# SmartIMU_TestBoard_Sch.net
KiCad netlist of a schematic drawn in Altium Designer
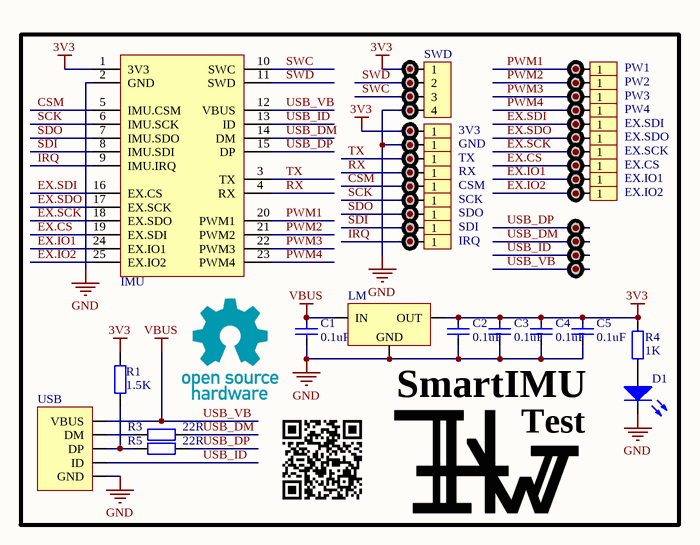
[diagram p0: SmartIMU_TestBoard_Sch.SchDoc]

(export (version "E")
  (design (tool "Eeschema 10.0.6"))
  (components
    (comp (ref "3V3")
      (value "HDR1X1_180_2.54")
      (footprint "PCB_Connector:HDR1X1_180_2.54")
      (description "Header")
      (libsource (lib "SCH_Connector") (part "HDR1X1_180_2.54"))
    )
    (comp (ref "C1")
      (value "0.1uF")
      (footprint "PCB_Passive:CAP_0603")
      (description "Capacitor")
      (fields (field (name "Comment") "Cap_0603"))
      (libsource (lib "SCH_Passive") (part "Cap_0603"))
    )
    (comp (ref "C2")
      (value "0.1uF")
      (footprint "PCB_Passive:CAP_0603")
      (description "Capacitor")
      (fields (field (name "Comment") "Cap_0603"))
      (libsource (lib "SCH_Passive") (part "Cap_0603"))
    )
    (comp (ref "C3")
      (value "0.1uF")
      (footprint "PCB_Passive:CAP_0603")
      (description "Capacitor")
      (fields (field (name "Comment") "Cap_0603"))
      (libsource (lib "SCH_Passive") (part "Cap_0603"))
    )
    (comp (ref "C4")
      (value "0.1uF")
      (footprint "PCB_Passive:CAP_0603")
      (description "Capacitor")
      (fields (field (name "Comment") "Cap_0603"))
      (libsource (lib "SCH_Passive") (part "Cap_0603"))
    )
    (comp (ref "C5")
      (value "0.1uF")
      (footprint "PCB_Passive:CAP_0603")
      (description "Capacitor")
      (fields (field (name "Comment") "Cap_0603"))
      (libsource (lib "SCH_Passive") (part "Cap_0603"))
    )
    (comp (ref "CSM")
      (value "HDR1X1_180_2.54")
      (footprint "PCB_Connector:HDR1X1_180_2.54")
      (description "Header")
      (libsource (lib "SCH_Connector") (part "HDR1X1_180_2.54"))
    )
    (comp (ref "D1")
      (value "LED_0603_BLUE")
      (footprint "PCB_Active:LED_0603_BLUE")
      (description "LED")
      (libsource (lib "SCH_Active") (part "LED_0603_BLUE"))
    )
    (comp (ref "EX.CS")
      (value "HDR1X1_180_2.54")
      (footprint "PCB_Connector:HDR1X1_180_2.54")
      (description "Header")
      (libsource (lib "SCH_Connector") (part "HDR1X1_180_2.54"))
    )
    (comp (ref "EX.IO1")
      (value "HDR1X1_180_2.54")
      (footprint "PCB_Connector:HDR1X1_180_2.54")
      (description "Header")
      (libsource (lib "SCH_Connector") (part "HDR1X1_180_2.54"))
    )
    (comp (ref "EX.IO2")
      (value "HDR1X1_180_2.54")
      (footprint "PCB_Connector:HDR1X1_180_2.54")
      (description "Header")
      (libsource (lib "SCH_Connector") (part "HDR1X1_180_2.54"))
    )
    (comp (ref "EX.SCK")
      (value "HDR1X1_180_2.54")
      (footprint "PCB_Connector:HDR1X1_180_2.54")
      (description "Header")
      (libsource (lib "SCH_Connector") (part "HDR1X1_180_2.54"))
    )
    (comp (ref "EX.SDI")
      (value "HDR1X1_180_2.54")
      (footprint "PCB_Connector:HDR1X1_180_2.54")
      (description "Header")
      (libsource (lib "SCH_Connector") (part "HDR1X1_180_2.54"))
    )
    (comp (ref "EX.SDO")
      (value "HDR1X1_180_2.54")
      (footprint "PCB_Connector:HDR1X1_180_2.54")
      (description "Header")
      (libsource (lib "SCH_Connector") (part "HDR1X1_180_2.54"))
    )
    (comp (ref "GND")
      (value "HDR1X1_180_2.54")
      (footprint "PCB_Connector:HDR1X1_180_2.54")
      (description "Header")
      (libsource (lib "SCH_Connector") (part "HDR1X1_180_2.54"))
    )
    (comp (ref "HW")
      (value "HW")
      (footprint "PCB_Logo:Logo_HW_v2.0")
      (description "Logo")
      (libsource (lib "SCH_Logo") (part "HW"))
    )
    (comp (ref "IMU")
      (value "SmartIMU_Full")
      (footprint "PCB_Module:SMART_IMU_FULL")
      (description "Module")
      (libsource (lib "SCH_Module") (part "SmartIMU_Full"))
    )
    (comp (ref "IRQ")
      (value "HDR1X1_180_2.54")
      (footprint "PCB_Connector:HDR1X1_180_2.54")
      (description "Header")
      (libsource (lib "SCH_Connector") (part "HDR1X1_180_2.54"))
    )
    (comp (ref "LM")
      (value "LM1117")
      (footprint "PCB_IC:SOT223")
      (description "Power")
      (libsource (lib "SCH_IC") (part "LM1117"))
    )
    (comp (ref "ORCODE")
      (value "SmartIMU_ORCODE")
      (description "Logo")
      (libsource (lib "SCH_Logo") (part "SmartIMU_ORCODE"))
    )
    (comp (ref "OSHW") (value "OSHW") (description "Logo") (libsource (lib "SCH_Logo") (part "OSHW")))
    (comp (ref "PW1")
      (value "HDR1X1_180_2.54")
      (footprint "PCB_Connector:HDR1X1_180_2.54")
      (description "Header")
      (libsource (lib "SCH_Connector") (part "HDR1X1_180_2.54"))
    )
    (comp (ref "PW2")
      (value "HDR1X1_180_2.54")
      (footprint "PCB_Connector:HDR1X1_180_2.54")
      (description "Header")
      (libsource (lib "SCH_Connector") (part "HDR1X1_180_2.54"))
    )
    (comp (ref "PW3")
      (value "HDR1X1_180_2.54")
      (footprint "PCB_Connector:HDR1X1_180_2.54")
      (description "Header")
      (libsource (lib "SCH_Connector") (part "HDR1X1_180_2.54"))
    )
    (comp (ref "PW4")
      (value "HDR1X1_180_2.54")
      (footprint "PCB_Connector:HDR1X1_180_2.54")
      (description "Header")
      (libsource (lib "SCH_Connector") (part "HDR1X1_180_2.54"))
    )
    (comp (ref "R1")
      (value "1.5K")
      (footprint "PCB_Passive:RES_0603")
      (description "Resistor")
      (fields (field (name "Comment") "Res_0603"))
      (libsource (lib "SCH_Passive") (part "Res_0603"))
    )
    (comp (ref "R3")
      (value "22R")
      (footprint "PCB_Passive:RES_0603")
      (description "Resistor")
      (fields (field (name "Comment") "Res_0603"))
      (libsource (lib "") (part "Res_0603_1"))
    )
    (comp (ref "R4")
      (value "1K")
      (footprint "PCB_Passive:RES_0603")
      (description "Resistor")
      (fields (field (name "Comment") "Res_0603"))
      (libsource (lib "SCH_Passive") (part "Res_0603"))
    )
    (comp (ref "R5")
      (value "22R")
      (footprint "PCB_Passive:RES_0603")
      (description "Resistor")
      (fields (field (name "Comment") "Res_0603"))
      (libsource (lib "") (part "Res_0603_1"))
    )
    (comp (ref "RX")
      (value "HDR1X1_180_2.54")
      (footprint "PCB_Connector:HDR1X1_180_2.54")
      (description "Header")
      (libsource (lib "SCH_Connector") (part "HDR1X1_180_2.54"))
    )
    (comp (ref "SCK")
      (value "HDR1X1_180_2.54")
      (footprint "PCB_Connector:HDR1X1_180_2.54")
      (description "Header")
      (libsource (lib "SCH_Connector") (part "HDR1X1_180_2.54"))
    )
    (comp (ref "SDI")
      (value "HDR1X1_180_2.54")
      (footprint "PCB_Connector:HDR1X1_180_2.54")
      (description "Header")
      (libsource (lib "SCH_Connector") (part "HDR1X1_180_2.54"))
    )
    (comp (ref "SDO")
      (value "HDR1X1_180_2.54")
      (footprint "PCB_Connector:HDR1X1_180_2.54")
      (description "Header")
      (libsource (lib "SCH_Connector") (part "HDR1X1_180_2.54"))
    )
    (comp (ref "SWD")
      (value "HDR1X4_90F_2.54")
      (footprint "PCB_Connector:HDR1X4_90F_2.54")
      (description "Header")
      (libsource (lib "SCH_Connector") (part "HDR1X4_90F_2.54"))
    )
    (comp (ref "TP1")
      (value "TestPoint_HalfH")
      (footprint "PCB_Connector:TestPoint_0.6mm_HelfH")
      (description "TestPoint")
      (libsource (lib "SCH_Connector") (part "TestPoint_HalfH"))
    )
    (comp (ref "TP2")
      (value "TestPoint_HalfH")
      (footprint "PCB_Connector:TestPoint_0.6mm_HelfH")
      (description "TestPoint")
      (libsource (lib "SCH_Connector") (part "TestPoint_HalfH"))
    )
    (comp (ref "TP3")
      (value "TestPoint_HalfH")
      (footprint "PCB_Connector:TestPoint_0.6mm_HelfH")
      (description "TestPoint")
      (libsource (lib "SCH_Connector") (part "TestPoint_HalfH"))
    )
    (comp (ref "TP4")
      (value "TestPoint_HalfH")
      (footprint "PCB_Connector:TestPoint_0.6mm_HelfH")
      (description "TestPoint")
      (libsource (lib "SCH_Connector") (part "TestPoint_HalfH"))
    )
    (comp (ref "TP5")
      (value "TestPoint_HalfH")
      (footprint "PCB_Connector:TestPoint_0.6mm_HelfH")
      (description "TestPoint")
      (libsource (lib "SCH_Connector") (part "TestPoint_HalfH"))
    )
    (comp (ref "TP6")
      (value "TestPoint_HalfH")
      (footprint "PCB_Connector:TestPoint_0.6mm_HelfH")
      (description "TestPoint")
      (libsource (lib "SCH_Connector") (part "TestPoint_HalfH"))
    )
    (comp (ref "TP7")
      (value "TestPoint_HalfH")
      (footprint "PCB_Connector:TestPoint_0.6mm_HelfH")
      (description "TestPoint")
      (libsource (lib "SCH_Connector") (part "TestPoint_HalfH"))
    )
    (comp (ref "TP8")
      (value "TestPoint_HalfH")
      (footprint "PCB_Connector:TestPoint_0.6mm_HelfH")
      (description "TestPoint")
      (libsource (lib "SCH_Connector") (part "TestPoint_HalfH"))
    )
    (comp (ref "TP9")
      (value "TestPoint_HalfH")
      (footprint "PCB_Connector:TestPoint_0.6mm_HelfH")
      (description "TestPoint")
      (libsource (lib "SCH_Connector") (part "TestPoint_HalfH"))
    )
    (comp (ref "TP10")
      (value "TestPoint_HalfH")
      (footprint "PCB_Connector:TestPoint_0.6mm_HelfH")
      (description "TestPoint")
      (libsource (lib "SCH_Connector") (part "TestPoint_HalfH"))
    )
    (comp (ref "TP11")
      (value "TestPoint_HalfH")
      (footprint "PCB_Connector:TestPoint_0.6mm_HelfH")
      (description "TestPoint")
      (libsource (lib "SCH_Connector") (part "TestPoint_HalfH"))
    )
    (comp (ref "TP12")
      (value "TestPoint_HalfH")
      (footprint "PCB_Connector:TestPoint_0.6mm_HelfH")
      (description "TestPoint")
      (libsource (lib "SCH_Connector") (part "TestPoint_HalfH"))
    )
    (comp (ref "TP13")
      (value "TestPoint_HalfH")
      (footprint "PCB_Connector:TestPoint_0.6mm_HelfH")
      (description "TestPoint")
      (libsource (lib "SCH_Connector") (part "TestPoint_HalfH"))
    )
    (comp (ref "TP14")
      (value "TestPoint_HalfH")
      (footprint "PCB_Connector:TestPoint_0.6mm_HelfH")
      (description "TestPoint")
      (libsource (lib "SCH_Connector") (part "TestPoint_HalfH"))
    )
    (comp (ref "TP15")
      (value "TestPoint_HalfH")
      (footprint "PCB_Connector:TestPoint_0.6mm_HelfH")
      (description "TestPoint")
      (libsource (lib "SCH_Connector") (part "TestPoint_HalfH"))
    )
    (comp (ref "TP16")
      (value "TestPoint_HalfH")
      (footprint "PCB_Connector:TestPoint_0.6mm_HelfH")
      (description "TestPoint")
      (libsource (lib "SCH_Connector") (part "TestPoint_HalfH"))
    )
    (comp (ref "TP17")
      (value "TestPoint_HalfH")
      (footprint "PCB_Connector:TestPoint_0.6mm_HelfH")
      (description "TestPoint")
      (libsource (lib "SCH_Connector") (part "TestPoint_HalfH"))
    )
    (comp (ref "TP18")
      (value "TestPoint_HalfH")
      (footprint "PCB_Connector:TestPoint_0.6mm_HelfH")
      (description "TestPoint")
      (libsource (lib "SCH_Connector") (part "TestPoint_HalfH"))
    )
    (comp (ref "TP19")
      (value "TestPoint_HalfH")
      (footprint "PCB_Connector:TestPoint_0.6mm_HelfH")
      (description "TestPoint")
      (libsource (lib "SCH_Connector") (part "TestPoint_HalfH"))
    )
    (comp (ref "TP20")
      (value "TestPoint_HalfH")
      (footprint "PCB_Connector:TestPoint_0.6mm_HelfH")
      (description "TestPoint")
      (libsource (lib "SCH_Connector") (part "TestPoint_HalfH"))
    )
    (comp (ref "TP21")
      (value "TestPoint_HalfH")
      (footprint "PCB_Connector:TestPoint_0.6mm_HelfH")
      (description "TestPoint")
      (libsource (lib "SCH_Connector") (part "TestPoint_HalfH"))
    )
    (comp (ref "TP22")
      (value "TestPoint_HalfH")
      (footprint "PCB_Connector:TestPoint_0.6mm_HelfH")
      (description "TestPoint")
      (libsource (lib "SCH_Connector") (part "TestPoint_HalfH"))
    )
    (comp (ref "TP23")
      (value "TestPoint_HalfH")
      (footprint "PCB_Connector:TestPoint_0.6mm_HelfH")
      (description "TestPoint")
      (libsource (lib "SCH_Connector") (part "TestPoint_HalfH"))
    )
    (comp (ref "TP24")
      (value "TestPoint_HalfH")
      (footprint "PCB_Connector:TestPoint_0.6mm_HelfH")
      (description "TestPoint")
      (libsource (lib "SCH_Connector") (part "TestPoint_HalfH"))
    )
    (comp (ref "TP25")
      (value "TestPoint_HalfH")
      (footprint "PCB_Connector:TestPoint_0.6mm_HelfH")
      (description "TestPoint")
      (libsource (lib "SCH_Connector") (part "TestPoint_HalfH"))
    )
    (comp (ref "TP26")
      (value "TestPoint_HalfH")
      (footprint "PCB_Connector:TestPoint_0.6mm_HelfH")
      (description "TestPoint")
      (libsource (lib "SCH_Connector") (part "TestPoint_HalfH"))
    )
    (comp (ref "TP27")
      (value "TestPoint_HalfH")
      (footprint "PCB_Connector:TestPoint_0.6mm_HelfH")
      (description "TestPoint")
      (libsource (lib "SCH_Connector") (part "TestPoint_HalfH"))
    )
    (comp (ref "TX")
      (value "HDR1X1_180_2.54")
      (footprint "PCB_Connector:HDR1X1_180_2.54")
      (description "Header")
      (libsource (lib "SCH_Connector") (part "HDR1X1_180_2.54"))
    )
    (comp (ref "USB")
      (value "USB_Micro")
      (footprint "PCB_USB:USB_Micro-AB")
      (description "USB")
      (libsource (lib "SCH_USB") (part "USB_Micro"))
    )
  )
  (nets
    (net (code "1") (name "/CSM") (class "Default")
      (node (ref "CSM") (pin "1") (pinfunction "1_1") (pintype "passive"))
      (node (ref "IMU") (pin "5") (pinfunction "IMU.CSM_5") (pintype "passive"))
      (node (ref "TP7") (pin "1") (pinfunction "TP_1") (pintype "passive"))
    )
    (net (code "2") (name "/EX.CS") (class "Default")
      (node (ref "EX.CS") (pin "1") (pinfunction "1_1") (pintype "passive"))
      (node (ref "IMU") (pin "19") (pinfunction "EX.SDI_19") (pintype "passive"))
      (node (ref "TP21") (pin "1") (pinfunction "TP_1") (pintype "passive"))
    )
    (net (code "3") (name "/EX.IO1") (class "Default")
      (node (ref "EX.IO1") (pin "1") (pinfunction "1_1") (pintype "passive"))
      (node (ref "IMU") (pin "24") (pinfunction "EX.IO1_24") (pintype "passive"))
      (node (ref "TP22") (pin "1") (pinfunction "TP_1") (pintype "passive"))
    )
    (net (code "4") (name "/EX.IO2") (class "Default")
      (node (ref "EX.IO2") (pin "1") (pinfunction "1_1") (pintype "passive"))
      (node (ref "IMU") (pin "25") (pinfunction "EX.IO2_25") (pintype "passive"))
      (node (ref "TP23") (pin "1") (pinfunction "TP_1") (pintype "passive"))
    )
    (net (code "5") (name "/EX.SCK") (class "Default")
      (node (ref "EX.SCK") (pin "1") (pinfunction "1_1") (pintype "passive"))
      (node (ref "IMU") (pin "18") (pinfunction "EX.SDO_18") (pintype "passive"))
      (node (ref "TP20") (pin "1") (pinfunction "TP_1") (pintype "passive"))
    )
    (net (code "6") (name "/EX.SDI") (class "Default")
      (node (ref "EX.SDI") (pin "1") (pinfunction "1_1") (pintype "passive"))
      (node (ref "IMU") (pin "16") (pinfunction "EX.CS_16") (pintype "passive"))
      (node (ref "TP18") (pin "1") (pinfunction "TP_1") (pintype "passive"))
    )
    (net (code "7") (name "/EX.SDO") (class "Default")
      (node (ref "EX.SDO") (pin "1") (pinfunction "1_1") (pintype "passive"))
      (node (ref "IMU") (pin "17") (pinfunction "EX.SCK_17") (pintype "passive"))
      (node (ref "TP19") (pin "1") (pinfunction "TP_1") (pintype "passive"))
    )
    (net (code "8") (name "/IRQ") (class "Default")
      (node (ref "IMU") (pin "9") (pinfunction "IMU.IRQ_9") (pintype "passive"))
      (node (ref "IRQ") (pin "1") (pinfunction "1_1") (pintype "passive"))
      (node (ref "TP11") (pin "1") (pinfunction "TP_1") (pintype "passive"))
    )
    (net (code "9") (name "/PWM1") (class "Default")
      (node (ref "IMU") (pin "20") (pinfunction "PWM1_20") (pintype "passive"))
      (node (ref "PW1") (pin "1") (pinfunction "1_1") (pintype "passive"))
      (node (ref "TP14") (pin "1") (pinfunction "TP_1") (pintype "passive"))
    )
    (net (code "10") (name "/PWM2") (class "Default")
      (node (ref "IMU") (pin "21") (pinfunction "PWM2_21") (pintype "passive"))
      (node (ref "PW2") (pin "1") (pinfunction "1_1") (pintype "passive"))
      (node (ref "TP15") (pin "1") (pinfunction "TP_1") (pintype "passive"))
    )
    (net (code "11") (name "/PWM3") (class "Default")
      (node (ref "IMU") (pin "22") (pinfunction "PWM3_22") (pintype "passive"))
      (node (ref "PW3") (pin "1") (pinfunction "1_1") (pintype "passive"))
      (node (ref "TP16") (pin "1") (pinfunction "TP_1") (pintype "passive"))
    )
    (net (code "12") (name "/PWM4") (class "Default")
      (node (ref "IMU") (pin "23") (pinfunction "PWM4_23") (pintype "passive"))
      (node (ref "PW4") (pin "1") (pinfunction "1_1") (pintype "passive"))
      (node (ref "TP17") (pin "1") (pinfunction "TP_1") (pintype "passive"))
    )
    (net (code "13") (name "/RX") (class "Default")
      (node (ref "IMU") (pin "4") (pinfunction "RX_4") (pintype "passive"))
      (node (ref "RX") (pin "1") (pinfunction "1_1") (pintype "passive"))
      (node (ref "TP12") (pin "1") (pinfunction "TP_1") (pintype "passive"))
    )
    (net (code "14") (name "/SCK") (class "Default")
      (node (ref "IMU") (pin "6") (pinfunction "IMU.SCK_6") (pintype "passive"))
      (node (ref "SCK") (pin "1") (pinfunction "1_1") (pintype "passive"))
      (node (ref "TP8") (pin "1") (pinfunction "TP_1") (pintype "passive"))
    )
    (net (code "15") (name "/SDI") (class "Default")
      (node (ref "IMU") (pin "8") (pinfunction "IMU.SDI_8") (pintype "passive"))
      (node (ref "SDI") (pin "1") (pinfunction "1_1") (pintype "passive"))
      (node (ref "TP10") (pin "1") (pinfunction "TP_1") (pintype "passive"))
    )
    (net (code "16") (name "/SDO") (class "Default")
      (node (ref "IMU") (pin "7") (pinfunction "IMU.SDO_7") (pintype "passive"))
      (node (ref "SDO") (pin "1") (pinfunction "1_1") (pintype "passive"))
      (node (ref "TP9") (pin "1") (pinfunction "TP_1") (pintype "passive"))
    )
    (net (code "17") (name "/SWC") (class "Default")
      (node (ref "IMU") (pin "10") (pinfunction "SWC_10") (pintype "passive"))
      (node (ref "SWD") (pin "3") (pinfunction "3_3") (pintype "passive"))
      (node (ref "TP3") (pin "1") (pinfunction "TP_1") (pintype "passive"))
    )
    (net (code "18") (name "/SWD") (class "Default")
      (node (ref "IMU") (pin "11") (pinfunction "SWD_11") (pintype "passive"))
      (node (ref "SWD") (pin "2") (pinfunction "2_2") (pintype "passive"))
      (node (ref "TP2") (pin "1") (pinfunction "TP_1") (pintype "passive"))
    )
    (net (code "19") (name "/TX") (class "Default")
      (node (ref "IMU") (pin "3") (pinfunction "TX_3") (pintype "passive"))
      (node (ref "TP13") (pin "1") (pinfunction "TP_1") (pintype "passive"))
      (node (ref "TX") (pin "1") (pinfunction "1_1") (pintype "passive"))
    )
    (net (code "20") (name "/USB_DM") (class "Default")
      (node (ref "IMU") (pin "14") (pinfunction "DM_14") (pintype "passive"))
      (node (ref "R3") (pin "2") (pinfunction "2_2") (pintype "passive"))
      (node (ref "TP25") (pin "1") (pinfunction "TP_1") (pintype "passive"))
    )
    (net (code "21") (name "/USB_DP") (class "Default")
      (node (ref "IMU") (pin "15") (pinfunction "DP_15") (pintype "passive"))
      (node (ref "R5") (pin "2") (pinfunction "2_2") (pintype "passive"))
      (node (ref "TP24") (pin "1") (pinfunction "TP_1") (pintype "passive"))
    )
    (net (code "22") (name "/USB_ID") (class "Default")
      (node (ref "IMU") (pin "13") (pinfunction "ID_13") (pintype "passive"))
      (node (ref "TP26") (pin "1") (pinfunction "TP_1") (pintype "passive"))
      (node (ref "USB") (pin "4") (pinfunction "ID_4") (pintype "passive"))
    )
    (net (code "23") (name "3V3") (class "Default")
      (node (ref "3V3") (pin "1") (pinfunction "1_1") (pintype "passive"))
      (node (ref "C2") (pin "2") (pinfunction "2_2") (pintype "passive"))
      (node (ref "C3") (pin "2") (pinfunction "2_2") (pintype "passive"))
      (node (ref "C4") (pin "2") (pinfunction "2_2") (pintype "passive"))
      (node (ref "C5") (pin "2") (pinfunction "2_2") (pintype "passive"))
      (node (ref "IMU") (pin "1") (pinfunction "3V3_1") (pintype "passive"))
      (node (ref "LM") (pin "2") (pinfunction "OUT_2") (pintype "power_in"))
      (node (ref "R1") (pin "2") (pinfunction "2_2") (pintype "passive"))
      (node (ref "R4") (pin "2") (pinfunction "2_2") (pintype "passive"))
      (node (ref "SWD") (pin "1") (pinfunction "1_1") (pintype "passive"))
      (node (ref "TP1") (pin "1") (pinfunction "TP_1") (pintype "passive"))
      (node (ref "TP5") (pin "1") (pinfunction "TP_1") (pintype "passive"))
    )
    (net (code "24") (name "GND") (class "Default")
      (node (ref "C1") (pin "2") (pinfunction "2_2") (pintype "passive"))
      (node (ref "C2") (pin "1") (pinfunction "1_1") (pintype "passive"))
      (node (ref "C3") (pin "1") (pinfunction "1_1") (pintype "passive"))
      (node (ref "C4") (pin "1") (pinfunction "1_1") (pintype "passive"))
      (node (ref "C5") (pin "1") (pinfunction "1_1") (pintype "passive"))
      (node (ref "D1") (pin "2") (pinfunction "K_2") (pintype "passive"))
      (node (ref "GND") (pin "1") (pinfunction "1_1") (pintype "passive"))
      (node (ref "IMU") (pin "2") (pinfunction "GND_2") (pintype "passive"))
      (node (ref "LM") (pin "1") (pinfunction "GND_1") (pintype "power_in"))
      (node (ref "SWD") (pin "4") (pinfunction "4_4") (pintype "passive"))
      (node (ref "TP4") (pin "1") (pinfunction "TP_1") (pintype "passive"))
      (node (ref "TP6") (pin "1") (pinfunction "TP_1") (pintype "passive"))
      (node (ref "USB") (pin "5") (pinfunction "GND_5") (pintype "passive"))
    )
    (net (code "25") (name "Net-(D1-A)") (class "Default")
      (node (ref "D1") (pin "1") (pinfunction "A_1") (pintype "passive"))
      (node (ref "R4") (pin "1") (pinfunction "1_1") (pintype "passive"))
    )
    (net (code "26") (name "Net-(USB-DM)") (class "Default")
      (node (ref "R3") (pin "1") (pinfunction "1_1") (pintype "passive"))
      (node (ref "USB") (pin "2") (pinfunction "DM_2") (pintype "passive"))
    )
    (net (code "27") (name "Net-(USB-DP)") (class "Default")
      (node (ref "R1") (pin "1") (pinfunction "1_1") (pintype "passive"))
      (node (ref "R5") (pin "1") (pinfunction "1_1") (pintype "passive"))
      (node (ref "USB") (pin "3") (pinfunction "DP_3") (pintype "passive"))
    )
    (net (code "28") (name "VBUS") (class "Default")
      (node (ref "C1") (pin "1") (pinfunction "1_1") (pintype "passive"))
      (node (ref "IMU") (pin "12") (pinfunction "VBUS_12") (pintype "passive"))
      (node (ref "LM") (pin "3") (pinfunction "IN_3") (pintype "power_in"))
      (node (ref "TP27") (pin "1") (pinfunction "TP_1") (pintype "passive"))
      (node (ref "USB") (pin "1") (pinfunction "VBUS_1") (pintype "passive"))
    )
  )
)
